# l2_pcb_v4.net
KiCad netlist of a schematic drawn in EAGLE
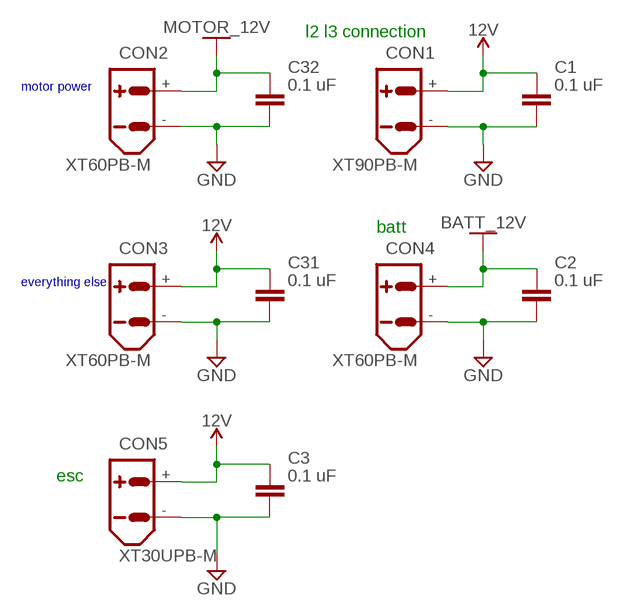
[diagram p0: schematic, sheet 1]

(export (version "E")
  (design (tool "Eeschema 10.0.6"))
  (components
    (comp (ref "C1")
      (value "0.1 uF")
      (footprint "eagle-import:CAPC1608X85")
      (libsource (lib "eagle-import") (part "CCHIP-0603(1608-METRIC)_"))
    )
    (comp (ref "C2")
      (value "0.1 uF")
      (footprint "eagle-import:CAPC1608X85")
      (libsource (lib "eagle-import") (part "CCHIP-0603(1608-METRIC)_"))
    )
    (comp (ref "C3")
      (value "0.1 uF")
      (footprint "eagle-import:CAPC1608X85")
      (libsource (lib "eagle-import") (part "CCHIP-0603(1608-METRIC)_"))
    )
    (comp (ref "C31")
      (value "0.1 uF")
      (footprint "eagle-import:CAPC1608X85")
      (libsource (lib "eagle-import") (part "CCHIP-0603(1608-METRIC)_"))
    )
    (comp (ref "C32")
      (value "0.1 uF")
      (footprint "eagle-import:CAPC1608X85")
      (libsource (lib "eagle-import") (part "CCHIP-0603(1608-METRIC)_"))
    )
    (comp (ref "CON1")
      (value "XT90PB-M")
      (footprint "eagle-import:XT90PB-M")
      (libsource (lib "eagle-import") (part "XT90PB-M"))
    )
    (comp (ref "CON2")
      (value "XT60PB-M")
      (footprint "eagle-import:XT60PB-M")
      (libsource (lib "eagle-import") (part "XT60PB-M"))
    )
    (comp (ref "CON3")
      (value "XT60PB-M")
      (footprint "eagle-import:XT60PB-M")
      (libsource (lib "eagle-import") (part "XT60PB-M"))
    )
    (comp (ref "CON4")
      (value "XT60PB-M")
      (footprint "eagle-import:XT60PB-M")
      (libsource (lib "eagle-import") (part "XT60PB-M"))
    )
    (comp (ref "CON5")
      (value "XT30UPB-M")
      (footprint "eagle-import:XT30UPB-M")
      (libsource (lib "eagle-import") (part "XT30UPB-M"))
    )
  )
  (nets
    (net (code "1") (name "12V") (class "Default")
      (node (ref "C1") (pin "1") (pinfunction "1_1") (pintype "passive"))
      (node (ref "C3") (pin "1") (pinfunction "1_1") (pintype "passive"))
      (node (ref "C31") (pin "1") (pinfunction "1_1") (pintype "passive"))
      (node (ref "CON1") (pin "+") (pinfunction "+_+") (pintype "power_in"))
      (node (ref "CON3") (pin "+") (pinfunction "+_+") (pintype "power_in"))
      (node (ref "CON5") (pin "+") (pinfunction "+_+") (pintype "power_in"))
    )
    (net (code "2") (name "BATT_12V") (class "Default")
      (node (ref "C2") (pin "1") (pinfunction "1_1") (pintype "passive"))
      (node (ref "CON4") (pin "+") (pinfunction "+_+") (pintype "power_in"))
    )
    (net (code "3") (name "GND") (class "Default")
      (node (ref "C1") (pin "2") (pinfunction "2_2") (pintype "passive"))
      (node (ref "C2") (pin "2") (pinfunction "2_2") (pintype "passive"))
      (node (ref "C3") (pin "2") (pinfunction "2_2") (pintype "passive"))
      (node (ref "C31") (pin "2") (pinfunction "2_2") (pintype "passive"))
      (node (ref "C32") (pin "2") (pinfunction "2_2") (pintype "passive"))
      (node (ref "CON1") (pin "-") (pinfunction "-_-") (pintype "power_in"))
      (node (ref "CON2") (pin "-") (pinfunction "-_-") (pintype "power_in"))
      (node (ref "CON3") (pin "-") (pinfunction "-_-") (pintype "power_in"))
      (node (ref "CON4") (pin "-") (pinfunction "-_-") (pintype "power_in"))
      (node (ref "CON5") (pin "-") (pinfunction "-_-") (pintype "power_in"))
    )
    (net (code "4") (name "MOTOR_12V") (class "Default")
      (node (ref "C32") (pin "1") (pinfunction "1_1") (pintype "passive"))
      (node (ref "CON2") (pin "+") (pinfunction "+_+") (pintype "power_in"))
    )
  )
)
